# Grove_-_Rotary_Angle_Sensor_v1_2.net
KiCad netlist of a schematic drawn in EAGLE
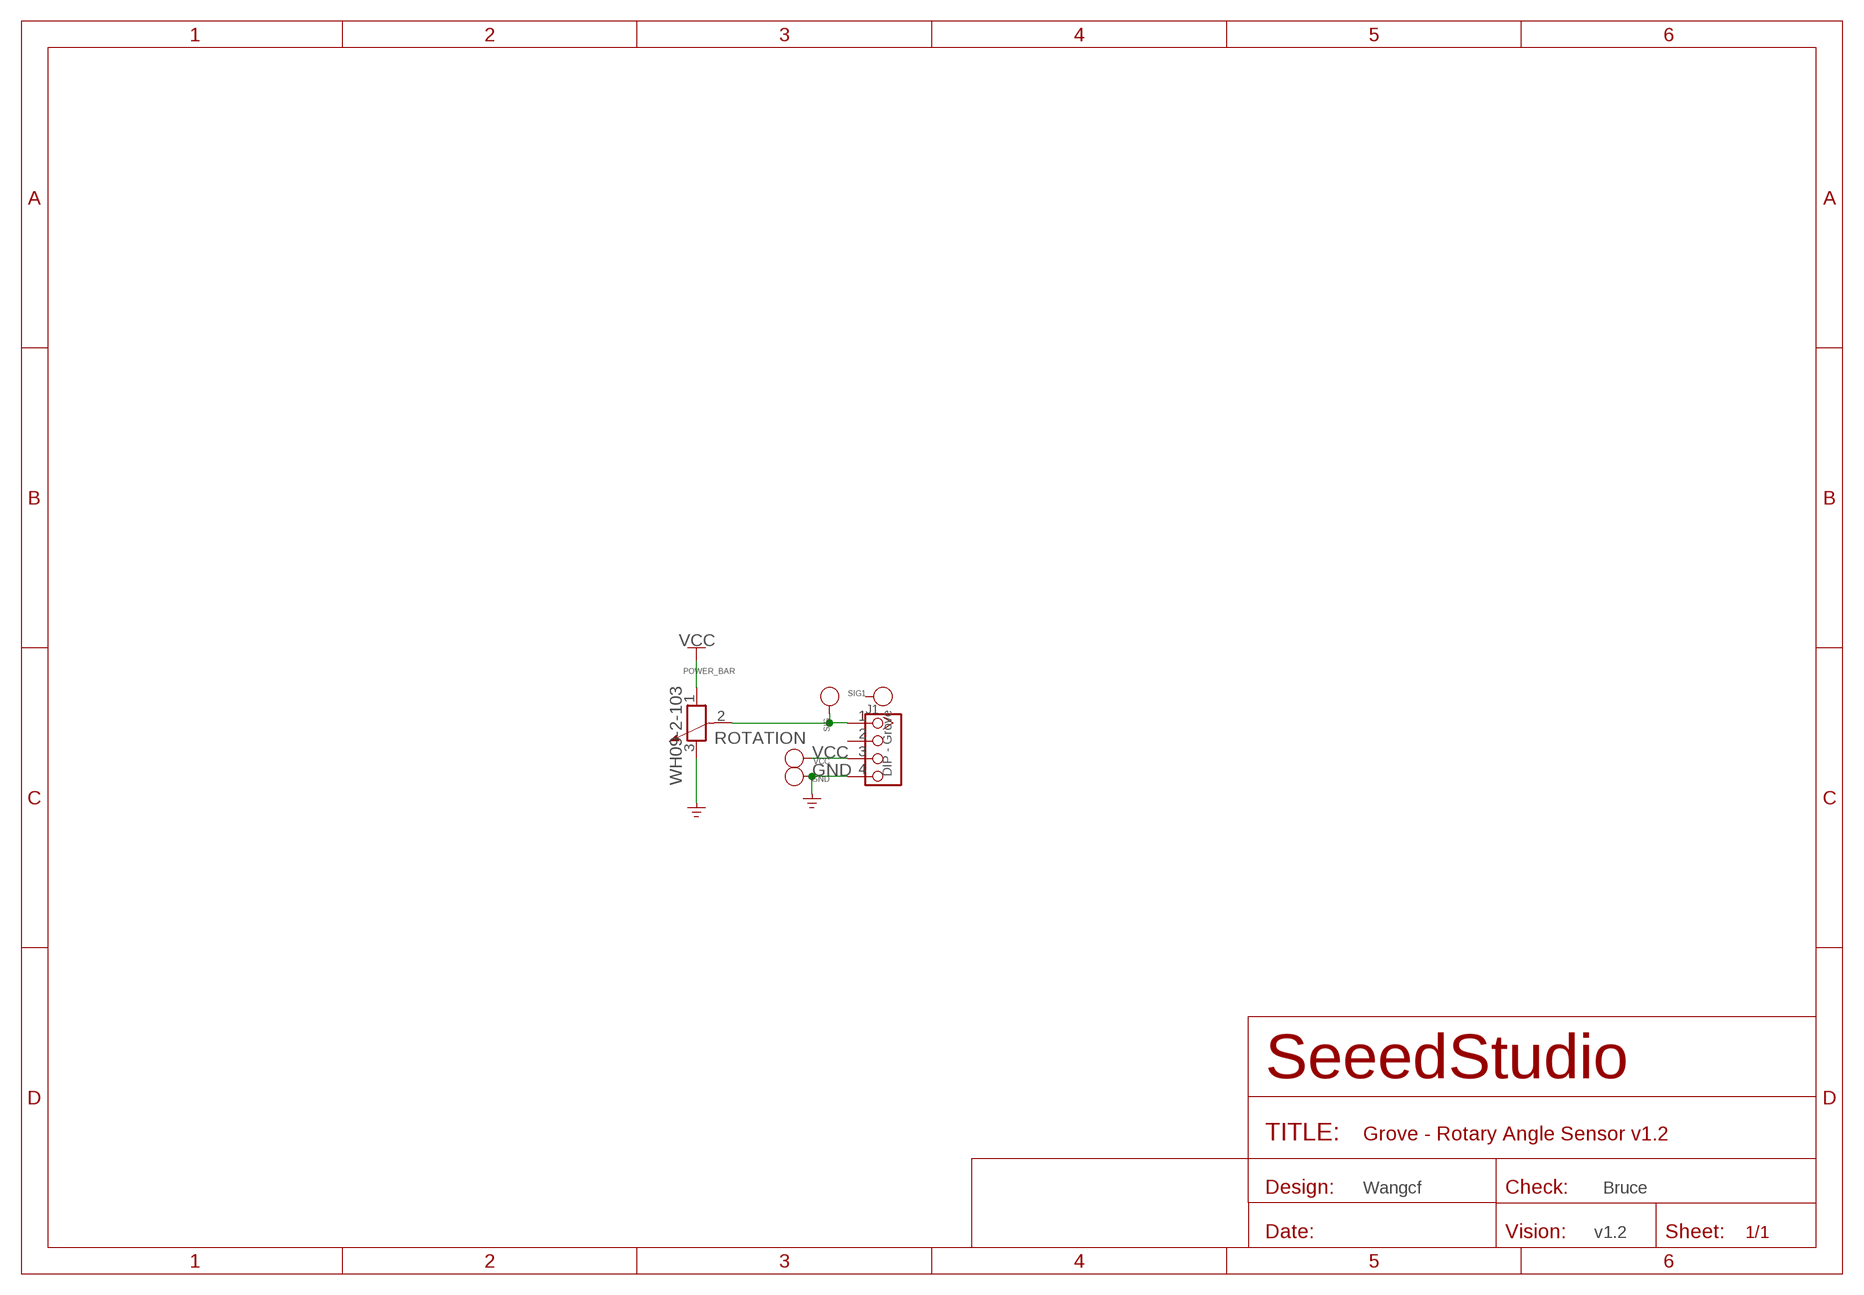
[diagram p0: schematic, sheet 1]

(export (version "E")
  (design (tool "Eeschema 10.0.6"))
  (components
    (comp (ref "GND")
      (value "PAD-TEST-POINT'4545'")
      (footprint "eagle-import:TP_4545")
      (fields (field (name "PARTNO") "DNP"))
      (libsource (lib "eagle-import") (part "PAD-TEST-POINT'4545'"))
    )
    (comp (ref "J1")
      (value "DIP - Grove")
      (footprint "eagle-import:4P-2.0")
      (libsource (lib "eagle-import") (part "TWIG-4P-2.0-2.0"))
    )
    (comp (ref "ROTATION")
      (value "WH09-2-103")
      (footprint "eagle-import:3P-SQUA-11X9.8X12H")
      (libsource (lib "eagle-import") (part "R-POTENTIOMETER'WH09-2'"))
    )
    (comp (ref "SIG")
      (value "PAD-TEST-POINT'4545'")
      (footprint "eagle-import:TP_4545")
      (fields (field (name "PARTNO") "DNP"))
      (libsource (lib "eagle-import") (part "PAD-TEST-POINT'4545'"))
    )
    (comp (ref "SIG1")
      (value "PAD-TEST-POINT'4545'")
      (footprint "eagle-import:TP_4545")
      (fields (field (name "PARTNO") "DNP"))
      (libsource (lib "eagle-import") (part "PAD-TEST-POINT'4545'"))
    )
    (comp (ref "VCC")
      (value "PAD-TEST-POINT'4545'")
      (footprint "eagle-import:TP_4545")
      (fields (field (name "PARTNO") "DNP"))
      (libsource (lib "eagle-import") (part "PAD-TEST-POINT'4545'"))
    )
  )
  (nets
    (net (code "1") (name "GND_POWER") (class "Default")
      (node (ref "GND") (pin "T") (pinfunction "T_T") (pintype "bidirectional"))
      (node (ref "J1") (pin "4") (pinfunction "4_4") (pintype "bidirectional"))
      (node (ref "ROTATION") (pin "3") (pinfunction "2_3") (pintype "passive"))
    )
    (net (code "2") (name "Net-(ROTATION-3)") (class "Default")
      (node (ref "J1") (pin "1") (pinfunction "1_1") (pintype "bidirectional"))
      (node (ref "ROTATION") (pin "2") (pinfunction "3_2") (pintype "passive"))
      (node (ref "SIG") (pin "T") (pinfunction "T_T") (pintype "bidirectional"))
    )
    (net (code "3") (name "POWER_BAR") (class "Default")
      (node (ref "J1") (pin "3") (pinfunction "3_3") (pintype "bidirectional"))
      (node (ref "ROTATION") (pin "1") (pinfunction "1_1") (pintype "passive"))
      (node (ref "VCC") (pin "T") (pinfunction "T_T") (pintype "bidirectional"))
    )
    (net (code "4") (name "unconnected-(J1-Pad2)") (class "Default")
      (node (ref "J1") (pin "2") (pinfunction "2_2") (pintype "bidirectional"))
    )
    (net (code "5") (name "unconnected-(SIG1-PadT)") (class "Default")
      (node (ref "SIG1") (pin "T") (pinfunction "T_T") (pintype "bidirectional"))
    )
  )
)
